# SL_LCD_SW_LED_2E.net
KiCad netlist of a schematic drawn in Altium Designer
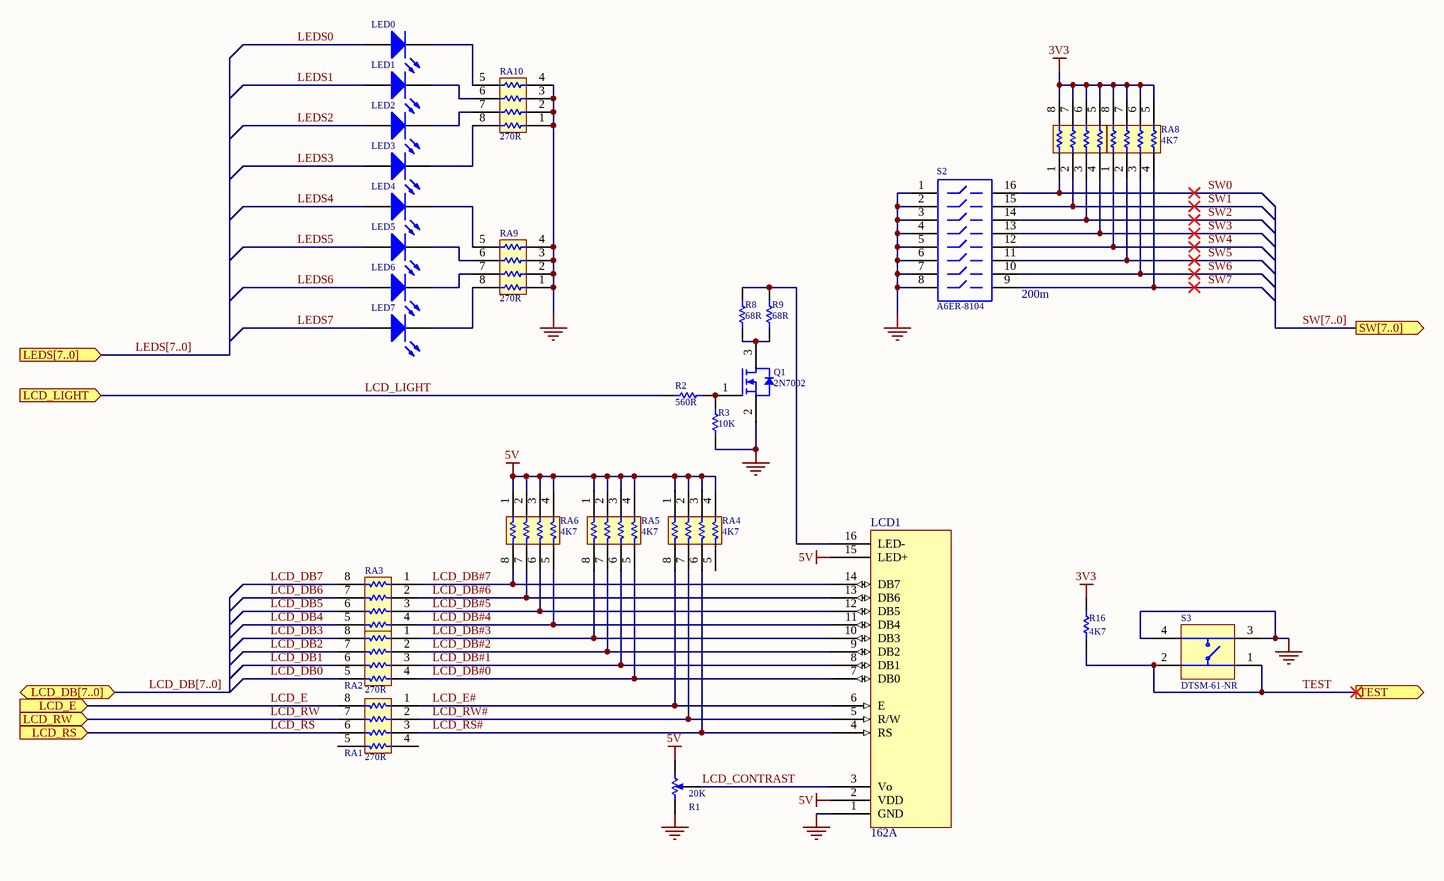
[diagram p0: SL_LCD_SW_LED_2E.SchDoc]

(export (version "E")
  (design (tool "Eeschema 10.0.6"))
  (components
    (comp (ref "LCD1")
      (value "162A")
      (footprint "Altium Nanoboard Project:162A")
      (description "16 char * 2 line LCD character display with b/light")
      (libsource (lib "Altium Nanoboard Project") (part "162A"))
    )
    (comp (ref "LED0")
      (value "HSMH-C170")
      (footprint "Altium Nanoboard Project:SMD _LED")
      (description "Typical RED GaAs SMD LED Agilent make")
      (libsource (lib "Altium Nanoboard Project") (part "HSMX-C670"))
    )
    (comp (ref "LED1")
      (value "HSMH-C170")
      (footprint "Altium Nanoboard Project:SMD _LED")
      (description "Typical RED GaAs SMD LED Agilent make")
      (libsource (lib "Altium Nanoboard Project") (part "HSMX-C670"))
    )
    (comp (ref "LED2")
      (value "HSMH-C170")
      (footprint "Altium Nanoboard Project:SMD _LED")
      (description "Typical RED GaAs SMD LED Agilent make")
      (libsource (lib "Altium Nanoboard Project") (part "HSMX-C670"))
    )
    (comp (ref "LED3")
      (value "HSMH-C170")
      (footprint "Altium Nanoboard Project:SMD _LED")
      (description "Typical RED GaAs SMD LED Agilent make")
      (libsource (lib "Altium Nanoboard Project") (part "HSMX-C670"))
    )
    (comp (ref "LED4")
      (value "HSMH-C170")
      (footprint "Altium Nanoboard Project:SMD _LED")
      (description "Typical RED GaAs SMD LED Agilent make")
      (libsource (lib "Altium Nanoboard Project") (part "HSMX-C670"))
    )
    (comp (ref "LED5")
      (value "HSMH-C170")
      (footprint "Altium Nanoboard Project:SMD _LED")
      (description "Typical RED GaAs SMD LED Agilent make")
      (libsource (lib "Altium Nanoboard Project") (part "HSMX-C670"))
    )
    (comp (ref "LED6")
      (value "HSMH-C170")
      (footprint "Altium Nanoboard Project:SMD _LED")
      (description "Typical RED GaAs SMD LED Agilent make")
      (libsource (lib "Altium Nanoboard Project") (part "HSMX-C670"))
    )
    (comp (ref "LED7")
      (value "HSMH-C170")
      (footprint "Altium Nanoboard Project:SMD _LED")
      (description "Typical RED GaAs SMD LED Agilent make")
      (libsource (lib "Altium Nanoboard Project") (part "HSMX-C670"))
    )
    (comp (ref "Q1")
      (value "2N7002")
      (footprint "Altium Nanoboard Project:SO-G3")
      (description "N Channel Mosfet")
      (libsource (lib "Altium Nanoboard Project") (part "2N7002"))
    )
    (comp (ref "R1")
      (value "20K")
      (footprint "POT4MM-2")
      (description "Square Trimming Potentiometer")
      (libsource (lib "Miscellaneous Devices") (part "RPot SM"))
    )
    (comp (ref "R2")
      (value "560R")
      (footprint "Altium Nanoboard Project:CC2012-0805")
      (description "Resistor")
      (libsource (lib "Altium Nanoboard Project") (part "RES"))
    )
    (comp (ref "R3")
      (value "10K")
      (footprint "Altium Nanoboard Project:CC2012-0805")
      (description "Resistor")
      (libsource (lib "Altium Nanoboard Project") (part "RES"))
    )
    (comp (ref "R8")
      (value "68R")
      (footprint "Altium Nanoboard Project:CC2012-0805")
      (description "Resistor")
      (libsource (lib "") (part "RES_1"))
    )
    (comp (ref "R9")
      (value "68R")
      (footprint "Altium Nanoboard Project:CC2012-0805")
      (description "Resistor")
      (libsource (lib "") (part "RES_1"))
    )
    (comp (ref "R16")
      (value "4K7")
      (footprint "Altium Nanoboard Project:CC2012-0805")
      (description "Resistor")
      (libsource (lib "Altium Nanoboard Project") (part "RES"))
    )
    (comp (ref "RA1")
      (value "270R")
      (footprint "Altium Nanoboard Project:MNR34")
      (description "3216x4 Resistor Array")
      (libsource (lib "") (part "MNR34_1"))
    )
    (comp (ref "RA2")
      (value "270R")
      (footprint "Altium Nanoboard Project:MNR34")
      (description "3216x4 Resistor Array")
      (libsource (lib "") (part "MNR34_1"))
    )
    (comp (ref "RA3")
      (value "270R")
      (footprint "Altium Nanoboard Project:MNR34")
      (description "3216x4 Resistor Array")
      (libsource (lib "") (part "MNR34_1"))
    )
    (comp (ref "RA4")
      (value "4K7")
      (footprint "MNR34T")
      (description "3216x4 Resistor Array")
      (libsource (lib "") (part "MNR34_2"))
    )
    (comp (ref "RA5")
      (value "4K7")
      (footprint "MNR34T")
      (description "3216x4 Resistor Array")
      (libsource (lib "") (part "MNR34_2"))
    )
    (comp (ref "RA6")
      (value "4K7")
      (footprint "MNR34T")
      (description "3216x4 Resistor Array")
      (libsource (lib "") (part "MNR34_2"))
    )
    (comp (ref "RA7")
      (value "4K7")
      (footprint "MNR34T")
      (description "3216x4 Resistor Array")
      (libsource (lib "") (part "MNR34_3"))
    )
    (comp (ref "RA8")
      (value "4K7")
      (footprint "MNR34T")
      (description "3216x4 Resistor Array")
      (libsource (lib "") (part "MNR34_3"))
    )
    (comp (ref "RA9")
      (value "270R")
      (footprint "MNR34T")
      (description "3216x4 Resistor Array")
      (libsource (lib "Altium Nanoboard Project") (part "MNR34"))
    )
    (comp (ref "RA10")
      (value "270R")
      (footprint "MNR34T")
      (description "3216x4 Resistor Array")
      (libsource (lib "Altium Nanoboard Project") (part "MNR34"))
    )
    (comp (ref "S2")
      (value "A6ER-8104")
      (footprint "Altium Nanoboard Project:DIP-16-KEY")
      (description "DIP Switch Side actuator long liver Piano Key")
      (fields (field (name "ALTIUM_VALUE") "200m"))
      (libsource (lib "Altium Nanoboard Project") (part "A6ER-8104"))
    )
    (comp (ref "S3")
      (value "DTSM-61-NR")
      (footprint "Altium Nanoboard Project:B3FS_SWITCH")
      (description "SPNA SMD Keyboard Switch")
      (libsource (lib "Altium Nanoboard Project") (part "B3FS"))
    )
  )
  (nets
    (net (code "1") (name "/LCD_CONTRAST") (class "Default")
      (node (ref "LCD1") (pin "3") (pinfunction "Vo_3") (pintype "tri_state"))
      (node (ref "R1") (pin "W") (pintype "passive"))
    )
    (net (code "2") (name "/LCD_DB#0") (class "Default")
      (node (ref "LCD1") (pin "7") (pinfunction "DB0_7") (pintype "bidirectional"))
      (node (ref "RA2") (pin "4") (pintype "passive"))
      (node (ref "RA5") (pin "5") (pintype "passive"))
    )
    (net (code "3") (name "/LCD_DB#1") (class "Default")
      (node (ref "LCD1") (pin "8") (pinfunction "DB1_8") (pintype "bidirectional"))
      (node (ref "RA2") (pin "3") (pintype "passive"))
      (node (ref "RA5") (pin "6") (pintype "passive"))
    )
    (net (code "4") (name "/LCD_DB#2") (class "Default")
      (node (ref "LCD1") (pin "9") (pinfunction "DB2_9") (pintype "bidirectional"))
      (node (ref "RA2") (pin "2") (pintype "passive"))
      (node (ref "RA5") (pin "7") (pintype "passive"))
    )
    (net (code "5") (name "/LCD_DB#3") (class "Default")
      (node (ref "LCD1") (pin "10") (pinfunction "DB3_10") (pintype "bidirectional"))
      (node (ref "RA2") (pin "1") (pintype "passive"))
      (node (ref "RA5") (pin "8") (pintype "passive"))
    )
    (net (code "6") (name "/LCD_DB#4") (class "Default")
      (node (ref "LCD1") (pin "11") (pinfunction "DB4_11") (pintype "bidirectional"))
      (node (ref "RA3") (pin "4") (pintype "passive"))
      (node (ref "RA6") (pin "5") (pintype "passive"))
    )
    (net (code "7") (name "/LCD_DB#5") (class "Default")
      (node (ref "LCD1") (pin "12") (pinfunction "DB5_12") (pintype "bidirectional"))
      (node (ref "RA3") (pin "3") (pintype "passive"))
      (node (ref "RA6") (pin "6") (pintype "passive"))
    )
    (net (code "8") (name "/LCD_DB#6") (class "Default")
      (node (ref "LCD1") (pin "13") (pinfunction "DB6_13") (pintype "bidirectional"))
      (node (ref "RA3") (pin "2") (pintype "passive"))
      (node (ref "RA6") (pin "7") (pintype "passive"))
    )
    (net (code "9") (name "/LCD_DB#7") (class "Default")
      (node (ref "LCD1") (pin "14") (pinfunction "DB7_14") (pintype "bidirectional"))
      (node (ref "RA3") (pin "1") (pintype "passive"))
      (node (ref "RA6") (pin "8") (pintype "passive"))
    )
    (net (code "10") (name "/LCD_DB0") (class "Default") (node (ref "RA2") (pin "5") (pintype "passive")))
    (net (code "11") (name "/LCD_DB1") (class "Default") (node (ref "RA2") (pin "6") (pintype "passive")))
    (net (code "12") (name "/LCD_DB2") (class "Default") (node (ref "RA2") (pin "7") (pintype "passive")))
    (net (code "13") (name "/LCD_DB3") (class "Default") (node (ref "RA2") (pin "8") (pintype "passive")))
    (net (code "14") (name "/LCD_DB4") (class "Default") (node (ref "RA3") (pin "5") (pintype "passive")))
    (net (code "15") (name "/LCD_DB5") (class "Default") (node (ref "RA3") (pin "6") (pintype "passive")))
    (net (code "16") (name "/LCD_DB6") (class "Default") (node (ref "RA3") (pin "7") (pintype "passive")))
    (net (code "17") (name "/LCD_DB7") (class "Default") (node (ref "RA3") (pin "8") (pintype "passive")))
    (net (code "19") (name "/LCD_E") (class "Default") (node (ref "RA1") (pin "8") (pintype "passive")))
    (net (code "20") (name "/LCD_E#") (class "Default")
      (node (ref "LCD1") (pin "6") (pinfunction "E_6") (pintype "input"))
      (node (ref "RA1") (pin "1") (pintype "passive"))
      (node (ref "RA4") (pin "8") (pintype "passive"))
    )
    (net (code "21") (name "/LCD_LIGHT") (class "Default")
      (node (ref "R2") (pin "1") (pinfunction "1_1") (pintype "passive"))
    )
    (net (code "22") (name "/LCD_RS") (class "Default") (node (ref "RA1") (pin "6") (pintype "passive")))
    (net (code "23") (name "/LCD_RS#") (class "Default")
      (node (ref "LCD1") (pin "4") (pinfunction "RS_4") (pintype "input"))
      (node (ref "RA1") (pin "3") (pintype "passive"))
      (node (ref "RA4") (pin "6") (pintype "passive"))
    )
    (net (code "24") (name "/LCD_RW") (class "Default") (node (ref "RA1") (pin "7") (pintype "passive")))
    (net (code "25") (name "/LCD_RW#") (class "Default")
      (node (ref "LCD1") (pin "5") (pinfunction "R/W_5") (pintype "input"))
      (node (ref "RA1") (pin "2") (pintype "passive"))
      (node (ref "RA4") (pin "7") (pintype "passive"))
    )
    (net (code "26") (name "/LEDS0") (class "Default")
      (node (ref "LED0") (pin "1") (pinfunction "A_1") (pintype "passive"))
    )
    (net (code "27") (name "/LEDS1") (class "Default")
      (node (ref "LED1") (pin "1") (pinfunction "A_1") (pintype "passive"))
    )
    (net (code "28") (name "/LEDS2") (class "Default")
      (node (ref "LED2") (pin "1") (pinfunction "A_1") (pintype "passive"))
    )
    (net (code "29") (name "/LEDS3") (class "Default")
      (node (ref "LED3") (pin "1") (pinfunction "A_1") (pintype "passive"))
    )
    (net (code "30") (name "/LEDS4") (class "Default")
      (node (ref "LED4") (pin "1") (pinfunction "A_1") (pintype "passive"))
    )
    (net (code "31") (name "/LEDS5") (class "Default")
      (node (ref "LED5") (pin "1") (pinfunction "A_1") (pintype "passive"))
    )
    (net (code "32") (name "/LEDS6") (class "Default")
      (node (ref "LED6") (pin "1") (pinfunction "A_1") (pintype "passive"))
    )
    (net (code "33") (name "/LEDS7") (class "Default")
      (node (ref "LED7") (pin "1") (pinfunction "A_1") (pintype "passive"))
    )
    (net (code "35") (name "/SW0") (class "Default")
      (node (ref "RA7") (pin "1") (pintype "passive"))
      (node (ref "S2") (pin "16") (pinfunction "16_16") (pintype "passive"))
    )
    (net (code "36") (name "/SW1") (class "Default")
      (node (ref "RA7") (pin "2") (pintype "passive"))
      (node (ref "S2") (pin "15") (pinfunction "15_15") (pintype "passive"))
    )
    (net (code "37") (name "/SW2") (class "Default")
      (node (ref "RA7") (pin "3") (pintype "passive"))
      (node (ref "S2") (pin "14") (pinfunction "14_14") (pintype "passive"))
    )
    (net (code "38") (name "/SW3") (class "Default")
      (node (ref "RA7") (pin "4") (pintype "passive"))
      (node (ref "S2") (pin "13") (pinfunction "13_13") (pintype "passive"))
    )
    (net (code "39") (name "/SW4") (class "Default")
      (node (ref "RA8") (pin "1") (pintype "passive"))
      (node (ref "S2") (pin "12") (pinfunction "12_12") (pintype "passive"))
    )
    (net (code "40") (name "/SW5") (class "Default")
      (node (ref "RA8") (pin "2") (pintype "passive"))
      (node (ref "S2") (pin "11") (pinfunction "11_11") (pintype "passive"))
    )
    (net (code "41") (name "/SW6") (class "Default")
      (node (ref "RA8") (pin "3") (pintype "passive"))
      (node (ref "S2") (pin "10") (pinfunction "10_10") (pintype "passive"))
    )
    (net (code "42") (name "/SW7") (class "Default")
      (node (ref "RA8") (pin "4") (pintype "passive"))
      (node (ref "S2") (pin "9") (pinfunction "9_9") (pintype "passive"))
    )
    (net (code "44") (name "/TEST") (class "Default")
      (node (ref "R16") (pin "2") (pinfunction "2_2") (pintype "passive"))
      (node (ref "S3") (pin "1") (pinfunction "1_1") (pintype "passive"))
      (node (ref "S3") (pin "2") (pinfunction "2_2") (pintype "passive"))
    )
    (net (code "45") (name "3V3") (class "Default")
      (node (ref "R16") (pin "1") (pinfunction "1_1") (pintype "passive"))
      (node (ref "RA7") (pin "5") (pintype "passive"))
      (node (ref "RA7") (pin "6") (pintype "passive"))
      (node (ref "RA7") (pin "7") (pintype "passive"))
      (node (ref "RA7") (pin "8") (pintype "passive"))
      (node (ref "RA8") (pin "5") (pintype "passive"))
      (node (ref "RA8") (pin "6") (pintype "passive"))
      (node (ref "RA8") (pin "7") (pintype "passive"))
      (node (ref "RA8") (pin "8") (pintype "passive"))
    )
    (net (code "46") (name "5V") (class "Default")
      (node (ref "LCD1") (pin "15") (pinfunction "LED+_15") (pintype "power_in"))
      (node (ref "LCD1") (pin "2") (pinfunction "VDD_2") (pintype "power_in"))
      (node (ref "R1") (pin "CW") (pinfunction "+_CW") (pintype "passive"))
      (node (ref "RA4") (pin "1") (pintype "passive"))
      (node (ref "RA4") (pin "2") (pintype "passive"))
      (node (ref "RA4") (pin "3") (pintype "passive"))
      (node (ref "RA4") (pin "4") (pintype "passive"))
      (node (ref "RA5") (pin "1") (pintype "passive"))
      (node (ref "RA5") (pin "2") (pintype "passive"))
      (node (ref "RA5") (pin "3") (pintype "passive"))
      (node (ref "RA5") (pin "4") (pintype "passive"))
      (node (ref "RA6") (pin "1") (pintype "passive"))
      (node (ref "RA6") (pin "2") (pintype "passive"))
      (node (ref "RA6") (pin "3") (pintype "passive"))
      (node (ref "RA6") (pin "4") (pintype "passive"))
    )
    (net (code "47") (name "GND") (class "Default")
      (node (ref "LCD1") (pin "1") (pinfunction "GND_1") (pintype "power_in"))
      (node (ref "Q1") (pin "2") (pintype "passive"))
      (node (ref "R1") (pin "CCW") (pinfunction "-_CCW") (pintype "passive"))
      (node (ref "R3") (pin "1") (pinfunction "1_1") (pintype "passive"))
      (node (ref "RA10") (pin "1") (pintype "passive"))
      (node (ref "RA10") (pin "2") (pintype "passive"))
      (node (ref "RA10") (pin "3") (pintype "passive"))
      (node (ref "RA10") (pin "4") (pintype "passive"))
      (node (ref "RA9") (pin "1") (pintype "passive"))
      (node (ref "RA9") (pin "2") (pintype "passive"))
      (node (ref "RA9") (pin "3") (pintype "passive"))
      (node (ref "RA9") (pin "4") (pintype "passive"))
      (node (ref "S2") (pin "1") (pinfunction "1_1") (pintype "passive"))
      (node (ref "S2") (pin "2") (pinfunction "2_2") (pintype "passive"))
      (node (ref "S2") (pin "3") (pinfunction "3_3") (pintype "passive"))
      (node (ref "S2") (pin "4") (pinfunction "4_4") (pintype "passive"))
      (node (ref "S2") (pin "5") (pinfunction "5_5") (pintype "passive"))
      (node (ref "S2") (pin "6") (pinfunction "6_6") (pintype "passive"))
      (node (ref "S2") (pin "7") (pinfunction "7_7") (pintype "passive"))
      (node (ref "S2") (pin "8") (pinfunction "8_8") (pintype "passive"))
      (node (ref "S3") (pin "3") (pinfunction "3_3") (pintype "passive"))
      (node (ref "S3") (pin "4") (pinfunction "4_4") (pintype "passive"))
    )
    (net (code "48") (name "Net-(LCD1-LED-)") (class "Default")
      (node (ref "LCD1") (pin "16") (pinfunction "LED-_16") (pintype "power_in"))
      (node (ref "R8") (pin "1") (pinfunction "1_1") (pintype "passive"))
      (node (ref "R9") (pin "1") (pinfunction "1_1") (pintype "passive"))
    )
    (net (code "49") (name "Net-(LED0-K)") (class "Default")
      (node (ref "LED0") (pin "2") (pinfunction "K_2") (pintype "passive"))
      (node (ref "RA10") (pin "5") (pintype "passive"))
    )
    (net (code "50") (name "Net-(LED1-K)") (class "Default")
      (node (ref "LED1") (pin "2") (pinfunction "K_2") (pintype "passive"))
      (node (ref "RA10") (pin "6") (pintype "passive"))
    )
    (net (code "51") (name "Net-(LED2-K)") (class "Default")
      (node (ref "LED2") (pin "2") (pinfunction "K_2") (pintype "passive"))
      (node (ref "RA10") (pin "7") (pintype "passive"))
    )
    (net (code "52") (name "Net-(LED3-K)") (class "Default")
      (node (ref "LED3") (pin "2") (pinfunction "K_2") (pintype "passive"))
      (node (ref "RA10") (pin "8") (pintype "passive"))
    )
    (net (code "53") (name "Net-(LED4-K)") (class "Default")
      (node (ref "LED4") (pin "2") (pinfunction "K_2") (pintype "passive"))
      (node (ref "RA9") (pin "5") (pintype "passive"))
    )
    (net (code "54") (name "Net-(LED5-K)") (class "Default")
      (node (ref "LED5") (pin "2") (pinfunction "K_2") (pintype "passive"))
      (node (ref "RA9") (pin "6") (pintype "passive"))
    )
    (net (code "55") (name "Net-(LED6-K)") (class "Default")
      (node (ref "LED6") (pin "2") (pinfunction "K_2") (pintype "passive"))
      (node (ref "RA9") (pin "7") (pintype "passive"))
    )
    (net (code "56") (name "Net-(LED7-K)") (class "Default")
      (node (ref "LED7") (pin "2") (pinfunction "K_2") (pintype "passive"))
      (node (ref "RA9") (pin "8") (pintype "passive"))
    )
    (net (code "57") (name "Net-(Q1-Pad1)") (class "Default")
      (node (ref "Q1") (pin "1") (pintype "passive"))
      (node (ref "R2") (pin "2") (pinfunction "2_2") (pintype "passive"))
      (node (ref "R3") (pin "2") (pinfunction "2_2") (pintype "passive"))
    )
    (net (code "58") (name "Net-(Q1-Pad3)") (class "Default")
      (node (ref "Q1") (pin "3") (pintype "passive"))
      (node (ref "R8") (pin "2") (pinfunction "2_2") (pintype "passive"))
      (node (ref "R9") (pin "2") (pinfunction "2_2") (pintype "passive"))
    )
    (net (code "59") (name "unconnected-(RA1-Pad4)") (class "Default")
      (node (ref "RA1") (pin "4") (pintype "passive"))
    )
    (net (code "60") (name "unconnected-(RA1-Pad5)") (class "Default")
      (node (ref "RA1") (pin "5") (pintype "passive"))
    )
    (net (code "61") (name "unconnected-(RA4-Pad5)") (class "Default")
      (node (ref "RA4") (pin "5") (pintype "passive"))
    )
  )
)
